# GreenProbe.net
KiCad netlist of a schematic drawn in EAGLE
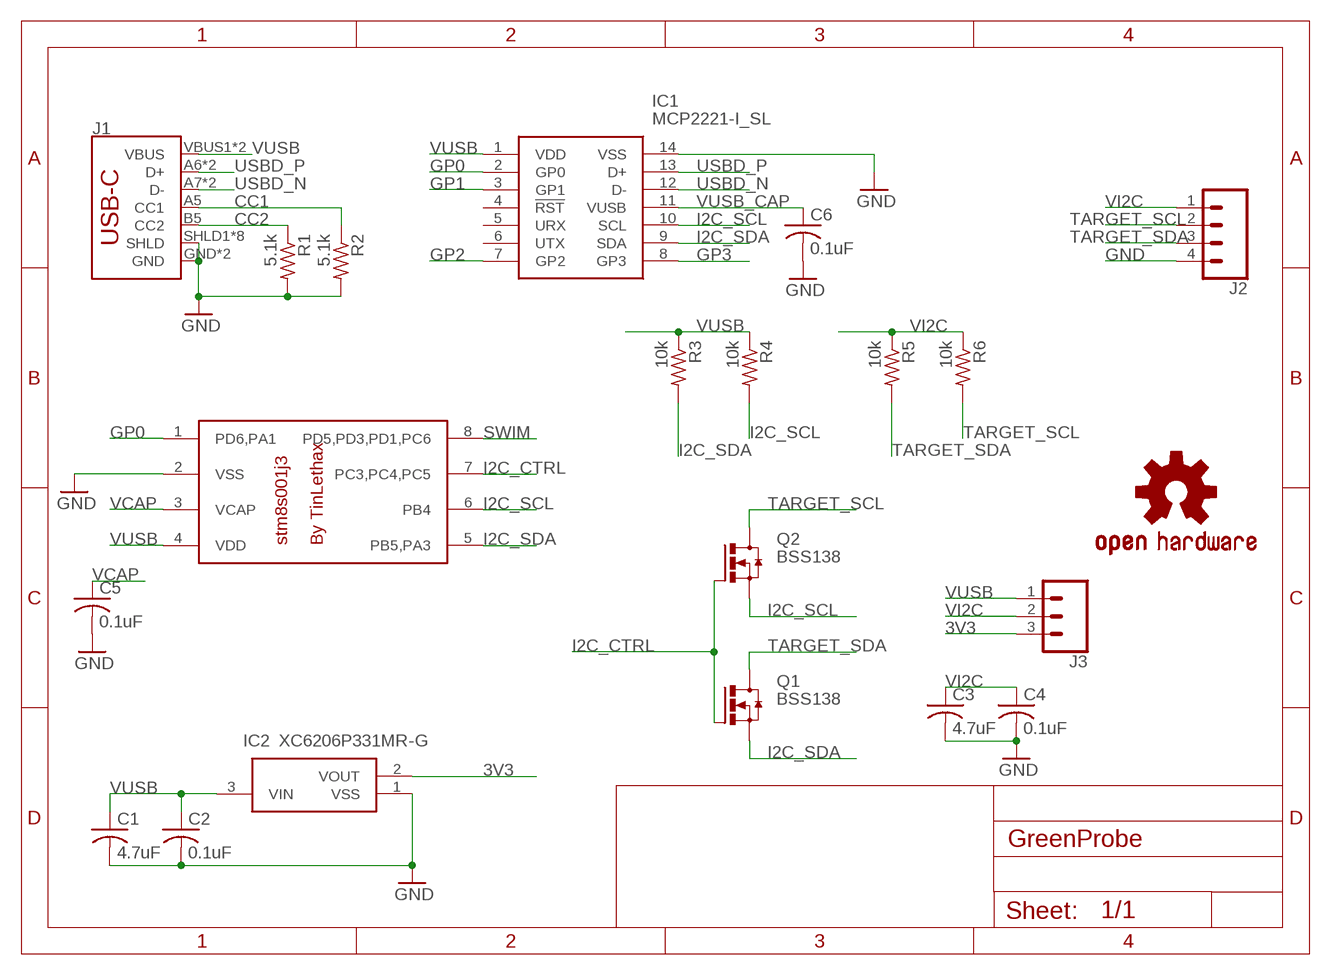
[diagram p0: schematic, sheet 1]

(export (version "E")
  (design (tool "Eeschema 10.0.6"))
  (components
    (comp (ref "C1")
      (value "4.7uF")
      (footprint "eagle-import:C0603")
      (libsource (lib "eagle-import") (part "C-USC0603"))
    )
    (comp (ref "C2")
      (value "0.1uF")
      (footprint "eagle-import:C0603")
      (libsource (lib "eagle-import") (part "C-USC0603"))
    )
    (comp (ref "C3")
      (value "4.7uF")
      (footprint "eagle-import:C0603")
      (libsource (lib "eagle-import") (part "C-USC0603"))
    )
    (comp (ref "C4")
      (value "0.1uF")
      (footprint "eagle-import:C0603")
      (libsource (lib "eagle-import") (part "C-USC0603"))
    )
    (comp (ref "C5")
      (value "0.1uF")
      (footprint "eagle-import:C0603")
      (libsource (lib "eagle-import") (part "C-USC0603"))
    )
    (comp (ref "C6")
      (value "0.1uF")
      (footprint "eagle-import:C0603")
      (libsource (lib "eagle-import") (part "C-USC0603"))
    )
    (comp (ref "IC1")
      (value "MCP2221-I_SL")
      (footprint "eagle-import:SOIC127P600X175-14N")
      (fields
        (field (name "ARROW_PART_NUMBER") "MCP2221-I/SL")
        (field (name "MOUSER_PART_NUMBER") "579-MCP2221-I/SL")
      )
      (libsource (lib "eagle-import") (part "MCP2221-I_SL"))
    )
    (comp (ref "IC2")
      (value "XC6206P331MR-G")
      (footprint "eagle-import:SOT95P280X130-3N")
      (fields (field (name "MOUSER_PART_NUMBER") "865-XC6206P331MR-G"))
      (libsource (lib "eagle-import") (part "XC6206P331MR-G"))
    )
    (comp (ref "IC3")
      (value "STM8S001J3")
      (footprint "eagle-import:SOP8")
      (libsource (lib "eagle-import") (part "STM8S001J3"))
    )
    (comp (ref "J1")
      (value "SPARKFUN-CONNECTORS_USB_C16PIN")
      (footprint "eagle-import:SPARKFUN-CONNECTORS_USB-C-16P")
      (libsource (lib "eagle-import") (part "SPARKFUN-CONNECTORS_USB_C16PIN"))
    )
    (comp (ref "J2")
      (value "CONN_041X04_NO_SILK")
      (footprint "eagle-import:1X04_NO_SILK")
      (libsource (lib "eagle-import") (part "CONN_041X04_NO_SILK"))
    )
    (comp (ref "J3")
      (value "CONN_031X03_NO_SILK")
      (footprint "eagle-import:1X03_NO_SILK")
      (libsource (lib "eagle-import") (part "CONN_031X03_NO_SILK"))
    )
    (comp (ref "LOGO1")
      (value "OSHW-LOGOMINI")
      (footprint "eagle-import:OSHW-LOGO-MINI")
      (libsource (lib "eagle-import") (part "OSHW-LOGOMINI"))
    )
    (comp (ref "Q1")
      (value "BSS138")
      (footprint "eagle-import:SOT23-3")
      (fields
        (field (name "DIGIKEY_PART_NUMBER") "BSS138CT-ND")
        (field (name "MANUFACTURER") "ON Semiconductor")
        (field (name "CREATED_BY") "PCBLayout.com")
      )
      (libsource (lib "eagle-import") (part "BSS138"))
    )
    (comp (ref "Q2")
      (value "BSS138")
      (footprint "eagle-import:SOT23-3")
      (fields
        (field (name "DIGIKEY_PART_NUMBER") "BSS138CT-ND")
        (field (name "MANUFACTURER") "ON Semiconductor")
        (field (name "CREATED_BY") "PCBLayout.com")
      )
      (libsource (lib "eagle-import") (part "BSS138"))
    )
    (comp (ref "R1")
      (value "5.1k")
      (footprint "eagle-import:R0603")
      (libsource (lib "eagle-import") (part "R-US_R0603"))
    )
    (comp (ref "R2")
      (value "5.1k")
      (footprint "eagle-import:R0603")
      (libsource (lib "eagle-import") (part "R-US_R0603"))
    )
    (comp (ref "R3")
      (value "10k")
      (footprint "eagle-import:R0603")
      (libsource (lib "eagle-import") (part "R-US_R0603"))
    )
    (comp (ref "R4")
      (value "10k")
      (footprint "eagle-import:R0603")
      (libsource (lib "eagle-import") (part "R-US_R0603"))
    )
    (comp (ref "R5")
      (value "10k")
      (footprint "eagle-import:R0603")
      (libsource (lib "eagle-import") (part "R-US_R0603"))
    )
    (comp (ref "R6")
      (value "10k")
      (footprint "eagle-import:R0603")
      (libsource (lib "eagle-import") (part "R-US_R0603"))
    )
  )
  (nets
    (net (code "1") (name "/3V3") (class "Default")
      (node (ref "IC2") (pin "2") (pinfunction "VOUT_2") (pintype "output"))
      (node (ref "J3") (pin "3") (pinfunction "3_3") (pintype "passive"))
    )
    (net (code "2") (name "/CC1") (class "Default")
      (node (ref "J1") (pin "A5") (pinfunction "CC1_A5") (pintype "bidirectional"))
      (node (ref "R2") (pin "1") (pinfunction "1_1") (pintype "passive"))
    )
    (net (code "3") (name "/CC2") (class "Default")
      (node (ref "J1") (pin "B5") (pinfunction "CC2_B5") (pintype "bidirectional"))
      (node (ref "R1") (pin "1") (pinfunction "1_1") (pintype "passive"))
    )
    (net (code "4") (name "/GP0") (class "Default")
      (node (ref "IC1") (pin "2") (pinfunction "GP0_2") (pintype "bidirectional"))
      (node (ref "IC3") (pin "1") (pinfunction "PD6,PA1_1") (pintype "bidirectional"))
    )
    (net (code "5") (name "/GP1") (class "Default")
      (node (ref "IC1") (pin "3") (pinfunction "GP1_3") (pintype "bidirectional"))
    )
    (net (code "6") (name "/GP2") (class "Default")
      (node (ref "IC1") (pin "7") (pinfunction "GP2_7") (pintype "bidirectional"))
    )
    (net (code "7") (name "/GP3") (class "Default")
      (node (ref "IC1") (pin "8") (pinfunction "GP3_8") (pintype "bidirectional"))
    )
    (net (code "8") (name "/I2C_CTRL") (class "Default")
      (node (ref "IC3") (pin "7") (pinfunction "PC3,PC4,PC5_7") (pintype "bidirectional"))
      (node (ref "Q1") (pin "1") (pinfunction "G_1") (pintype "passive"))
      (node (ref "Q2") (pin "1") (pinfunction "G_1") (pintype "passive"))
    )
    (net (code "9") (name "/I2C_SCL") (class "Default")
      (node (ref "IC1") (pin "10") (pinfunction "SCL_10") (pintype "bidirectional"))
      (node (ref "IC3") (pin "6") (pinfunction "PB4_6") (pintype "bidirectional"))
      (node (ref "Q2") (pin "2") (pinfunction "S_2") (pintype "passive"))
      (node (ref "R4") (pin "2") (pinfunction "2_2") (pintype "passive"))
    )
    (net (code "10") (name "/I2C_SDA") (class "Default")
      (node (ref "IC1") (pin "9") (pinfunction "SDA_9") (pintype "bidirectional"))
      (node (ref "IC3") (pin "5") (pinfunction "PB5,PA3_5") (pintype "bidirectional"))
      (node (ref "Q1") (pin "2") (pinfunction "S_2") (pintype "passive"))
      (node (ref "R3") (pin "2") (pinfunction "2_2") (pintype "passive"))
    )
    (net (code "11") (name "/SWIM") (class "Default")
      (node (ref "IC3") (pin "8") (pinfunction "PD5,PD3,PD1,PC6_8") (pintype "bidirectional"))
    )
    (net (code "12") (name "/TARGET_SCL") (class "Default")
      (node (ref "J2") (pin "2") (pinfunction "2_2") (pintype "passive"))
      (node (ref "Q2") (pin "3") (pinfunction "D_3") (pintype "passive"))
      (node (ref "R6") (pin "2") (pinfunction "2_2") (pintype "passive"))
    )
    (net (code "13") (name "/TARGET_SDA") (class "Default")
      (node (ref "J2") (pin "3") (pinfunction "3_3") (pintype "passive"))
      (node (ref "Q1") (pin "3") (pinfunction "D_3") (pintype "passive"))
      (node (ref "R5") (pin "2") (pinfunction "2_2") (pintype "passive"))
    )
    (net (code "14") (name "/USBD_N") (class "Default")
      (node (ref "IC1") (pin "12") (pinfunction "D-_12") (pintype "bidirectional"))
      (node (ref "J1") (pin "A7") (pinfunction "D-_A7") (pintype "bidirectional"))
      (node (ref "J1") (pin "B7") (pinfunction "D-_B7") (pintype "bidirectional"))
    )
    (net (code "15") (name "/USBD_P") (class "Default")
      (node (ref "IC1") (pin "13") (pinfunction "D+_13") (pintype "bidirectional"))
      (node (ref "J1") (pin "A6") (pinfunction "D+_A6") (pintype "bidirectional"))
      (node (ref "J1") (pin "B6") (pinfunction "D+_B6") (pintype "bidirectional"))
    )
    (net (code "16") (name "/VCAP") (class "Default")
      (node (ref "C5") (pin "1") (pinfunction "1_1") (pintype "passive"))
      (node (ref "IC3") (pin "3") (pinfunction "VCAP_3") (pintype "bidirectional"))
    )
    (net (code "17") (name "/VI2C") (class "Default")
      (node (ref "C3") (pin "1") (pinfunction "1_1") (pintype "passive"))
      (node (ref "C4") (pin "1") (pinfunction "1_1") (pintype "passive"))
      (node (ref "J2") (pin "1") (pinfunction "1_1") (pintype "passive"))
      (node (ref "J3") (pin "2") (pinfunction "2_2") (pintype "passive"))
      (node (ref "R5") (pin "1") (pinfunction "1_1") (pintype "passive"))
      (node (ref "R6") (pin "1") (pinfunction "1_1") (pintype "passive"))
    )
    (net (code "18") (name "/VUSB") (class "Default")
      (node (ref "C1") (pin "1") (pinfunction "1_1") (pintype "passive"))
      (node (ref "C2") (pin "1") (pinfunction "1_1") (pintype "passive"))
      (node (ref "IC1") (pin "1") (pinfunction "VDD_1") (pintype "bidirectional"))
      (node (ref "IC2") (pin "3") (pinfunction "VIN_3") (pintype "bidirectional"))
      (node (ref "IC3") (pin "4") (pinfunction "VDD_4") (pintype "bidirectional"))
      (node (ref "J1") (pin "VBUS1") (pinfunction "VBUS_VBUS1") (pintype "bidirectional"))
      (node (ref "J1") (pin "VBUS2") (pinfunction "VBUS_VBUS2") (pintype "bidirectional"))
      (node (ref "J3") (pin "1") (pinfunction "1_1") (pintype "passive"))
      (node (ref "R3") (pin "1") (pinfunction "1_1") (pintype "passive"))
      (node (ref "R4") (pin "1") (pinfunction "1_1") (pintype "passive"))
    )
    (net (code "19") (name "/VUSB_CAP") (class "Default")
      (node (ref "C6") (pin "1") (pinfunction "1_1") (pintype "passive"))
      (node (ref "IC1") (pin "11") (pinfunction "VUSB_11") (pintype "bidirectional"))
    )
    (net (code "20") (name "GND") (class "Default")
      (node (ref "C1") (pin "2") (pinfunction "2_2") (pintype "passive"))
      (node (ref "C2") (pin "2") (pinfunction "2_2") (pintype "passive"))
      (node (ref "C3") (pin "2") (pinfunction "2_2") (pintype "passive"))
      (node (ref "C4") (pin "2") (pinfunction "2_2") (pintype "passive"))
      (node (ref "C5") (pin "2") (pinfunction "2_2") (pintype "passive"))
      (node (ref "C6") (pin "2") (pinfunction "2_2") (pintype "passive"))
      (node (ref "IC1") (pin "14") (pinfunction "VSS_14") (pintype "bidirectional"))
      (node (ref "IC2") (pin "1") (pinfunction "VSS_1") (pintype "power_in"))
      (node (ref "IC3") (pin "2") (pinfunction "VSS_2") (pintype "bidirectional"))
      (node (ref "J1") (pin "GND") (pinfunction "GND_GND") (pintype "bidirectional"))
      (node (ref "J1") (pin "GND2") (pinfunction "GND_GND2") (pintype "bidirectional"))
      (node (ref "J1") (pin "SHLD1") (pinfunction "SHLD_SHLD1") (pintype "bidirectional"))
      (node (ref "J1") (pin "SHLD2") (pinfunction "SHLD_SHLD2") (pintype "bidirectional"))
      (node (ref "J1") (pin "SHLD3") (pinfunction "SHLD_SHLD3") (pintype "bidirectional"))
      (node (ref "J1") (pin "SHLD4") (pinfunction "SHLD_SHLD4") (pintype "bidirectional"))
      (node (ref "J1") (pin "SHLD5") (pinfunction "SHLD_SHLD5") (pintype "bidirectional"))
      (node (ref "J1") (pin "SHLD6") (pinfunction "SHLD_SHLD6") (pintype "bidirectional"))
      (node (ref "J1") (pin "SHLD7") (pinfunction "SHLD_SHLD7") (pintype "bidirectional"))
      (node (ref "J1") (pin "SHLD8") (pinfunction "SHLD_SHLD8") (pintype "bidirectional"))
      (node (ref "J2") (pin "4") (pinfunction "4_4") (pintype "passive"))
      (node (ref "R1") (pin "2") (pinfunction "2_2") (pintype "passive"))
      (node (ref "R2") (pin "2") (pinfunction "2_2") (pintype "passive"))
    )
    (net (code "21") (name "unconnected-(IC1-URX-Pad5)") (class "Default")
      (node (ref "IC1") (pin "5") (pinfunction "URX_5") (pintype "bidirectional"))
    )
    (net (code "22") (name "unconnected-(IC1-UTX-Pad6)") (class "Default")
      (node (ref "IC1") (pin "6") (pinfunction "UTX_6") (pintype "bidirectional"))
    )
    (net (code "23") (name "unconnected-(IC1-~{RST}-Pad4)") (class "Default")
      (node (ref "IC1") (pin "4") (pinfunction "~{RST}_4") (pintype "bidirectional"))
    )
  )
)
